# Amplifier_1.net
KiCad netlist of a schematic drawn in Altium Designer
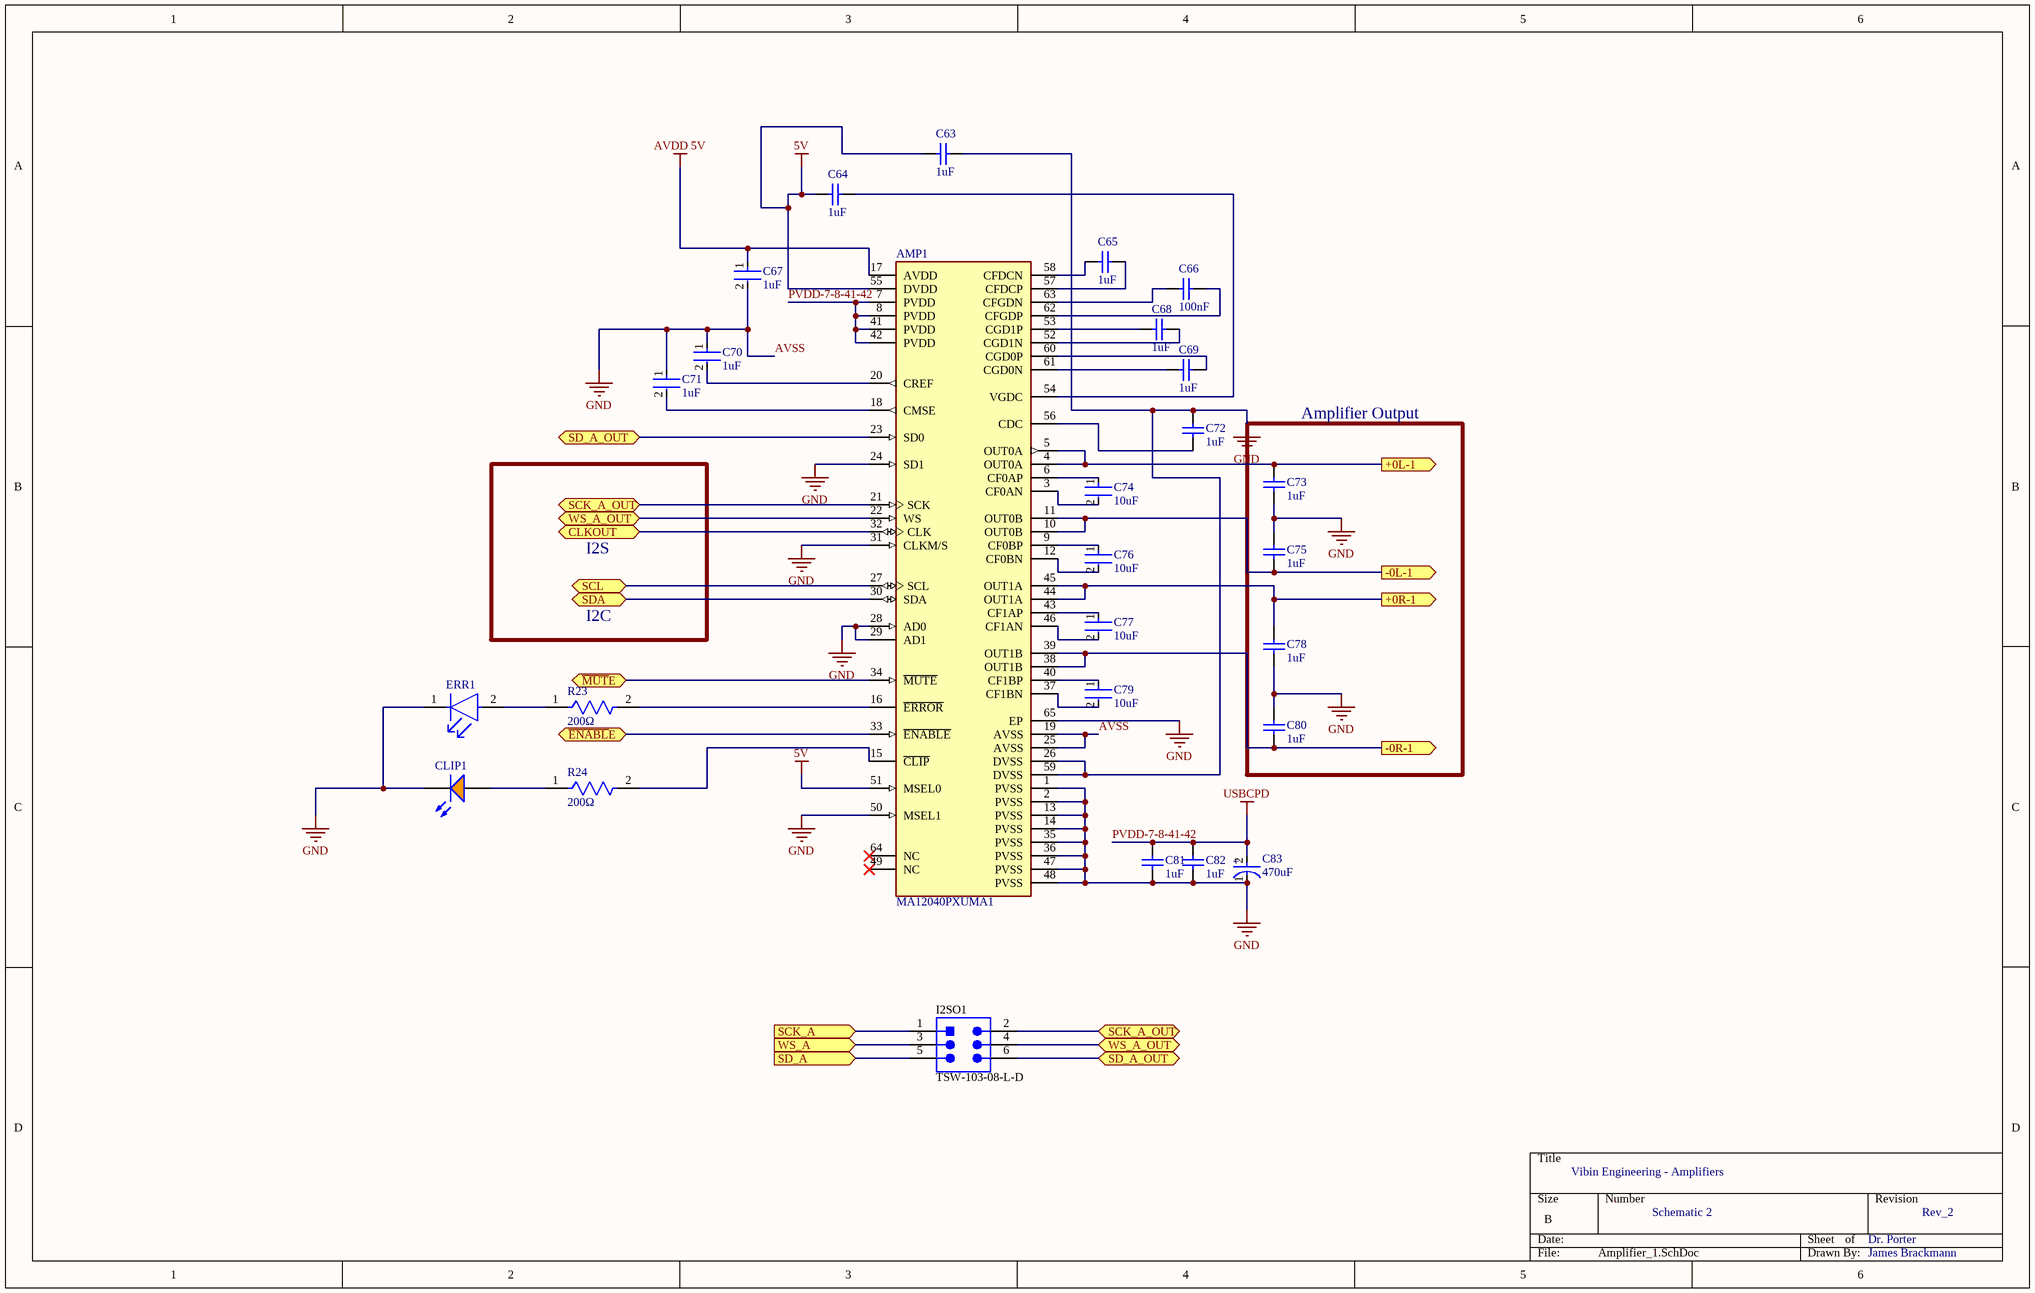
[diagram p0: Amplifier_1.SchDoc]

(export (version "E")
  (design (tool "Eeschema 10.0.6"))
  (components
    (comp (ref "AMP1")
      (value "MA12040PXUMA1")
      (footprint "FP-PG-VQFN-64-IPC_B")
      (description "IC AMP CLASS D STEREO 40W 64QFN")
      (fields
        (field (name "MANUFACTURER") "Infineon")
        (field (name "OCTOPART") "https://octopart.com/ma12040pxuma1-infineon-95984592")
      )
      (libsource (lib "Altium Content Vault") (part "7beef1d240aa861170d3bde7275adf3"))
    )
    (comp (ref "C63")
      (value "1uF")
      (footprint "CAPC1608X90X35LL15T15")
      (description "C0603C105K4RACTU")
      (fields (field (name "MANUFACTURER") "Kemet"))
      (libsource (lib "Altium Content Vault") (part "CAP"))
    )
    (comp (ref "C64")
      (value "1uF")
      (footprint "CAPC1608X90X35LL15T15")
      (description "C0603C105K4RACTU")
      (fields (field (name "MANUFACTURER") "Kemet"))
      (libsource (lib "Altium Content Vault") (part "CAP"))
    )
    (comp (ref "C65")
      (value "1uF")
      (footprint "CAPC1608X90X35LL15T15")
      (description "C0603C105K4RACTU")
      (fields (field (name "MANUFACTURER") "Kemet"))
      (libsource (lib "Altium Content Vault") (part "CAP"))
    )
    (comp (ref "C66")
      (value "100nF")
      (footprint "CAPC1608X90X35ML10T15")
      (fields
        (field (name "TOLERANCE") "10%")
        (field (name "VOLTAGE") "50V")
        (field (name "MANUFACTURER") "Murata")
      )
      (libsource (lib "Altium Content Vault") (part "CAP-NP-2"))
    )
    (comp (ref "C67")
      (value "1uF")
      (footprint "FP-GRM15-0_1-MFG")
      (description "CAP CER 1UF 10V X5R 0402         GRM155R61A105KE15D")
      (fields
        (field (name "OCTOPART") "https://octopart.com/grm155r61a105ke15d-murata-197442")
        (field (name "MANUFACTURER PART NUMBER") "GRM155R61A105KE15D")
      )
      (libsource (lib "Altium Content Vault") (part "02cd4be3c70576c341d710602a673aa"))
    )
    (comp (ref "C68")
      (value "1uF")
      (footprint "CAPC1608X90X35LL15T15")
      (description "C0603C105K4RACTU")
      (fields (field (name "MANUFACTURER") "Kemet"))
      (libsource (lib "Altium Content Vault") (part "CAP"))
    )
    (comp (ref "C69")
      (value "1uF")
      (footprint "CAPC1608X90X35LL15T15")
      (description "C0603C105K4RACTU")
      (fields (field (name "MANUFACTURER") "Kemet"))
      (libsource (lib "Altium Content Vault") (part "CAP"))
    )
    (comp (ref "C70")
      (value "1uF")
      (footprint "FP-GRM15-0_1-MFG")
      (description "CAP CER 1UF 10V X5R 0402         GRM155R61A105KE15D")
      (fields
        (field (name "OCTOPART") "https://octopart.com/grm155r61a105ke15d-murata-197442")
        (field (name "MANUFACTURER PART NUMBER") "GRM155R61A105KE15D")
      )
      (libsource (lib "Altium Content Vault") (part "02cd4be3c70576c341d710602a673aa"))
    )
    (comp (ref "C71")
      (value "1uF")
      (footprint "FP-GRM15-0_1-MFG")
      (description "CAP CER 1UF 10V X5R 0402         GRM155R61A105KE15D")
      (fields
        (field (name "OCTOPART") "https://octopart.com/grm155r61a105ke15d-murata-197442")
        (field (name "MANUFACTURER PART NUMBER") "GRM155R61A105KE15D")
      )
      (libsource (lib "Altium Content Vault") (part "02cd4be3c70576c341d710602a673aa"))
    )
    (comp (ref "C72")
      (value "1uF")
      (footprint "CAPC1608X90X35LL15T15")
      (description "C0603C105K4RACTU")
      (fields (field (name "MANUFACTURER") "Kemet"))
      (libsource (lib "Altium Content Vault") (part "CAP"))
    )
    (comp (ref "C73")
      (value "1uF")
      (footprint "CAPC1608X90X35LL15T15")
      (description "C0603C105K4RACTU")
      (fields (field (name "MANUFACTURER") "Kemet"))
      (libsource (lib "Altium Content Vault") (part "CAP"))
    )
    (comp (ref "C74")
      (value "10uF")
      (footprint "FP-1210-L_3_3_0_4-W_2_5_0-MFG")
      (description "General Purpose Ceramic Capacitor, 1210, 10uF, 10%, X5R, 15%, 25V        12103D106KAT2A")
      (fields (field (name "VOLTAGE") "25V") (field (name "TOLERANCE") "10%"))
      (libsource (lib "Altium Content Vault") (part "b4654b650e69147ec39a6b967a45e02"))
    )
    (comp (ref "C75")
      (value "1uF")
      (footprint "CAPC1608X90X35LL15T15")
      (description "C0603C105K4RACTU")
      (fields (field (name "MANUFACTURER") "Kemet"))
      (libsource (lib "Altium Content Vault") (part "CAP"))
    )
    (comp (ref "C76")
      (value "10uF")
      (footprint "FP-1210-L_3_3_0_4-W_2_5_0-MFG")
      (description "General Purpose Ceramic Capacitor, 1210, 10uF, 10%, X5R, 15%, 25V        12103D106KAT2A")
      (fields (field (name "VOLTAGE") "25V") (field (name "TOLERANCE") "10%"))
      (libsource (lib "Altium Content Vault") (part "b4654b650e69147ec39a6b967a45e02"))
    )
    (comp (ref "C77")
      (value "10uF")
      (footprint "FP-1210-L_3_3_0_4-W_2_5_0-MFG")
      (description "General Purpose Ceramic Capacitor, 1210, 10uF, 10%, X5R, 15%, 25V        12103D106KAT2A")
      (fields (field (name "VOLTAGE") "25V") (field (name "TOLERANCE") "10%"))
      (libsource (lib "Altium Content Vault") (part "b4654b650e69147ec39a6b967a45e02"))
    )
    (comp (ref "C78")
      (value "1uF")
      (footprint "CAPC1608X90X35LL15T15")
      (description "C0603C105K4RACTU")
      (fields (field (name "MANUFACTURER") "Kemet"))
      (libsource (lib "Altium Content Vault") (part "CAP"))
    )
    (comp (ref "C79")
      (value "10uF")
      (footprint "FP-1210-L_3_3_0_4-W_2_5_0-MFG")
      (description "General Purpose Ceramic Capacitor, 1210, 10uF, 10%, X5R, 15%, 25V        12103D106KAT2A")
      (fields (field (name "VOLTAGE") "25V") (field (name "TOLERANCE") "10%"))
      (libsource (lib "Altium Content Vault") (part "b4654b650e69147ec39a6b967a45e02"))
    )
    (comp (ref "C80")
      (value "1uF")
      (footprint "CAPC1608X90X35LL15T15")
      (description "C0603C105K4RACTU")
      (fields (field (name "MANUFACTURER") "Kemet"))
      (libsource (lib "Altium Content Vault") (part "CAP"))
    )
    (comp (ref "C81")
      (value "1uF")
      (footprint "CAPC1608X90X35LL15T15")
      (description "C0603C105K4RACTU")
      (fields (field (name "MANUFACTURER") "Kemet"))
      (libsource (lib "Altium Content Vault") (part "CAP"))
    )
    (comp (ref "C82")
      (value "1uF")
      (footprint "CAPC1608X90X35LL15T15")
      (description "C0603C105K4RACTU")
      (fields (field (name "MANUFACTURER") "Kemet"))
      (libsource (lib "Altium Content Vault") (part "CAP"))
    )
    (comp (ref "C83")
      (value "470uF")
      (footprint "FP-OS-CON-SMT-E12-MFG")
      (description "Conductive Polymer Aluminum Solid Capacitors (OS-CON) 470uF ±20% 20V      20SVPK470M")
      (fields (field (name "TOLERANCE") "20%"))
      (libsource (lib "Altium Content Vault") (part "a00bbbee19879c290e62620ae7e47b1"))
    )
    (comp (ref "CLIP1")
      (value "TLMO1100-GS08")
      (footprint "VISH-TLMX1100-2_V")
      (libsource (lib "Altium Content Vault") (part "LED-ORANGE-AK-2"))
    )
    (comp (ref "ERR1")
      (value "LTST-C190GKT")
      (footprint "FP-LTST-C190GKT-MFG")
      (description "LED GREEN CLEAR CHIP SMD       LTST-C190GKT")
      (fields (field (name "VOLTAGE") "2V"))
      (libsource (lib "Altium Content Vault") (part "8706943c75ba83719d021d2fdc84c58"))
    )
    (comp (ref "I2SO1")
      (value "TSW-103-08-L-D")
      (footprint "SMTC-TSW-103-08-L-D_V")
      (fields (field (name "MANUFACTURER") "Samtec"))
      (libsource (lib "Altium Content Vault") (part "CN-2P-M-R6"))
    )
    (comp (ref "R23")
      (value "200Ω")
      (footprint "FP-ERJ2RK-IPC_A")
      (description "RES SMD 200 OHM 1% 1/10W 0402      ERJ-2RKF2000X")
      (fields (field (name "TOLERANCE") "1%"))
      (libsource (lib "Altium Content Vault") (part "1029c3af85768c4190bb7ad29bc67b5"))
    )
    (comp (ref "R24")
      (value "200Ω")
      (footprint "FP-ERJ2RK-IPC_A")
      (description "RES SMD 200 OHM 1% 1/10W 0402    ERJ-2RKF2000X")
      (fields (field (name "TOLERANCE") "1%"))
      (libsource (lib "Altium Content Vault") (part "1029c3af85768c4190bb7ad29bc67b5"))
    )
  )
  (nets
    (net (code "1") (name "/+0L-1") (class "Default")
      (node (ref "AMP1") (pin "4") (pinfunction "OUT0A_4") (pintype "passive"))
      (node (ref "AMP1") (pin "5") (pinfunction "OUT0A_5") (pintype "output"))
      (node (ref "C73") (pin "1") (pinfunction "1_1") (pintype "passive"))
    )
    (net (code "2") (name "/+0R-1") (class "Default")
      (node (ref "AMP1") (pin "44") (pinfunction "OUT1A_44") (pintype "passive"))
      (node (ref "AMP1") (pin "45") (pinfunction "OUT1A_45") (pintype "passive"))
      (node (ref "C78") (pin "1") (pinfunction "1_1") (pintype "passive"))
    )
    (net (code "3") (name "/-0L-1") (class "Default")
      (node (ref "AMP1") (pin "10") (pinfunction "OUT0B_10") (pintype "passive"))
      (node (ref "AMP1") (pin "11") (pinfunction "OUT0B_11") (pintype "passive"))
      (node (ref "C75") (pin "2") (pinfunction "2_2") (pintype "passive"))
    )
    (net (code "4") (name "/-0R-1") (class "Default")
      (node (ref "AMP1") (pin "38") (pinfunction "OUT1B_38") (pintype "passive"))
      (node (ref "AMP1") (pin "39") (pinfunction "OUT1B_39") (pintype "passive"))
      (node (ref "C80") (pin "2") (pinfunction "2_2") (pintype "passive"))
    )
    (net (code "5") (name "/CLKOUT") (class "Default")
      (node (ref "AMP1") (pin "32") (pinfunction "CLK_32") (pintype "bidirectional"))
    )
    (net (code "6") (name "/SCK_A") (class "Default")
      (node (ref "I2SO1") (pin "1") (pinfunction "1_1") (pintype "passive"))
    )
    (net (code "7") (name "/SCK_A_OUT") (class "Default")
      (node (ref "AMP1") (pin "21") (pinfunction "SCK_21") (pintype "input"))
      (node (ref "I2SO1") (pin "2") (pinfunction "2_2") (pintype "passive"))
    )
    (net (code "8") (name "/SCL") (class "Default")
      (node (ref "AMP1") (pin "27") (pinfunction "SCL_27") (pintype "bidirectional"))
    )
    (net (code "9") (name "/SDA") (class "Default")
      (node (ref "AMP1") (pin "30") (pinfunction "SDA_30") (pintype "bidirectional"))
    )
    (net (code "10") (name "/SD_A") (class "Default")
      (node (ref "I2SO1") (pin "5") (pinfunction "5_5") (pintype "passive"))
    )
    (net (code "11") (name "/SD_A_OUT") (class "Default")
      (node (ref "AMP1") (pin "23") (pinfunction "SD0_23") (pintype "input"))
      (node (ref "I2SO1") (pin "6") (pinfunction "6_6") (pintype "passive"))
    )
    (net (code "12") (name "/WS_A") (class "Default")
      (node (ref "I2SO1") (pin "3") (pinfunction "3_3") (pintype "passive"))
    )
    (net (code "13") (name "/WS_A_OUT") (class "Default")
      (node (ref "AMP1") (pin "22") (pinfunction "WS_22") (pintype "input"))
      (node (ref "I2SO1") (pin "4") (pinfunction "4_4") (pintype "passive"))
    )
    (net (code "14") (name "/~{ENABL}E") (class "Default")
      (node (ref "AMP1") (pin "33") (pinfunction "~{ENABLE}_33") (pintype "input"))
    )
    (net (code "15") (name "/~{MUT}E") (class "Default")
      (node (ref "AMP1") (pin "34") (pinfunction "~{MUTE}_34") (pintype "input"))
    )
    (net (code "16") (name "5V") (class "Default")
      (node (ref "AMP1") (pin "51") (pinfunction "MSEL0_51") (pintype "input"))
      (node (ref "AMP1") (pin "55") (pinfunction "DVDD_55") (pintype "power_in"))
      (node (ref "C63") (pin "2") (pinfunction "2_2") (pintype "passive"))
      (node (ref "C64") (pin "1") (pinfunction "1_1") (pintype "passive"))
    )
    (net (code "17") (name "AVDD 5V") (class "Default")
      (node (ref "AMP1") (pin "17") (pinfunction "AVDD_17") (pintype "power_in"))
      (node (ref "C67") (pin "1") (pinfunction "1_1") (pintype "passive"))
    )
    (net (code "18") (name "GND") (class "Default")
      (node (ref "AMP1") (pin "1") (pinfunction "PVSS_1") (pintype "power_in"))
      (node (ref "AMP1") (pin "13") (pinfunction "PVSS_13") (pintype "power_in"))
      (node (ref "AMP1") (pin "14") (pinfunction "PVSS_14") (pintype "power_in"))
      (node (ref "AMP1") (pin "19") (pinfunction "AVSS_19") (pintype "power_in"))
      (node (ref "AMP1") (pin "2") (pinfunction "PVSS_2") (pintype "power_in"))
      (node (ref "AMP1") (pin "24") (pinfunction "SD1_24") (pintype "input"))
      (node (ref "AMP1") (pin "25") (pinfunction "AVSS_25") (pintype "power_in"))
      (node (ref "AMP1") (pin "26") (pinfunction "DVSS_26") (pintype "power_in"))
      (node (ref "AMP1") (pin "28") (pinfunction "AD0_28") (pintype "input"))
      (node (ref "AMP1") (pin "29") (pinfunction "AD1_29") (pintype "passive"))
      (node (ref "AMP1") (pin "31") (pinfunction "CLKM/S_31") (pintype "input"))
      (node (ref "AMP1") (pin "35") (pinfunction "PVSS_35") (pintype "power_in"))
      (node (ref "AMP1") (pin "36") (pinfunction "PVSS_36") (pintype "power_in"))
      (node (ref "AMP1") (pin "47") (pinfunction "PVSS_47") (pintype "power_in"))
      (node (ref "AMP1") (pin "48") (pinfunction "PVSS_48") (pintype "power_in"))
      (node (ref "AMP1") (pin "50") (pinfunction "MSEL1_50") (pintype "input"))
      (node (ref "AMP1") (pin "59") (pinfunction "DVSS_59") (pintype "power_in"))
      (node (ref "AMP1") (pin "65") (pinfunction "EP_65") (pintype "power_in"))
      (node (ref "C63") (pin "1") (pinfunction "1_1") (pintype "passive"))
      (node (ref "C67") (pin "2") (pinfunction "2_2") (pintype "passive"))
      (node (ref "C70") (pin "1") (pinfunction "1_1") (pintype "passive"))
      (node (ref "C71") (pin "1") (pinfunction "1_1") (pintype "passive"))
      (node (ref "C72") (pin "1") (pinfunction "1_1") (pintype "passive"))
      (node (ref "C73") (pin "2") (pinfunction "2_2") (pintype "passive"))
      (node (ref "C75") (pin "1") (pinfunction "1_1") (pintype "passive"))
      (node (ref "C78") (pin "2") (pinfunction "2_2") (pintype "passive"))
      (node (ref "C80") (pin "1") (pinfunction "1_1") (pintype "passive"))
      (node (ref "C81") (pin "2") (pinfunction "2_2") (pintype "passive"))
      (node (ref "C82") (pin "2") (pinfunction "2_2") (pintype "passive"))
      (node (ref "C83") (pin "1") (pinfunction "C_1") (pintype "passive"))
      (node (ref "CLIP1") (pin "2") (pinfunction "K_2") (pintype "passive"))
      (node (ref "ERR1") (pin "1") (pinfunction "C_1") (pintype "passive"))
    )
    (net (code "19") (name "Net-(AMP1-CDC)") (class "Default")
      (node (ref "AMP1") (pin "56") (pinfunction "CDC_56") (pintype "passive"))
      (node (ref "C72") (pin "2") (pinfunction "2_2") (pintype "passive"))
    )
    (net (code "20") (name "Net-(AMP1-CF0AN)") (class "Default")
      (node (ref "AMP1") (pin "3") (pinfunction "CF0AN_3") (pintype "passive"))
      (node (ref "C74") (pin "2") (pinfunction "2_2") (pintype "passive"))
    )
    (net (code "21") (name "Net-(AMP1-CF0AP)") (class "Default")
      (node (ref "AMP1") (pin "6") (pinfunction "CF0AP_6") (pintype "passive"))
      (node (ref "C74") (pin "1") (pinfunction "1_1") (pintype "passive"))
    )
    (net (code "22") (name "Net-(AMP1-CF0BN)") (class "Default")
      (node (ref "AMP1") (pin "12") (pinfunction "CF0BN_12") (pintype "passive"))
      (node (ref "C76") (pin "2") (pinfunction "2_2") (pintype "passive"))
    )
    (net (code "23") (name "Net-(AMP1-CF0BP)") (class "Default")
      (node (ref "AMP1") (pin "9") (pinfunction "CF0BP_9") (pintype "passive"))
      (node (ref "C76") (pin "1") (pinfunction "1_1") (pintype "passive"))
    )
    (net (code "24") (name "Net-(AMP1-CF1AN)") (class "Default")
      (node (ref "AMP1") (pin "46") (pinfunction "CF1AN_46") (pintype "passive"))
      (node (ref "C77") (pin "2") (pinfunction "2_2") (pintype "passive"))
    )
    (net (code "25") (name "Net-(AMP1-CF1AP)") (class "Default")
      (node (ref "AMP1") (pin "43") (pinfunction "CF1AP_43") (pintype "passive"))
      (node (ref "C77") (pin "1") (pinfunction "1_1") (pintype "passive"))
    )
    (net (code "26") (name "Net-(AMP1-CF1BN)") (class "Default")
      (node (ref "AMP1") (pin "37") (pinfunction "CF1BN_37") (pintype "passive"))
      (node (ref "C79") (pin "2") (pinfunction "2_2") (pintype "passive"))
    )
    (net (code "27") (name "Net-(AMP1-CF1BP)") (class "Default")
      (node (ref "AMP1") (pin "40") (pinfunction "CF1BP_40") (pintype "passive"))
      (node (ref "C79") (pin "1") (pinfunction "1_1") (pintype "passive"))
    )
    (net (code "28") (name "Net-(AMP1-CFDCN)") (class "Default")
      (node (ref "AMP1") (pin "58") (pinfunction "CFDCN_58") (pintype "passive"))
      (node (ref "C65") (pin "2") (pinfunction "2_2") (pintype "passive"))
    )
    (net (code "29") (name "Net-(AMP1-CFDCP)") (class "Default")
      (node (ref "AMP1") (pin "57") (pinfunction "CFDCP_57") (pintype "passive"))
      (node (ref "C65") (pin "1") (pinfunction "1_1") (pintype "passive"))
    )
    (net (code "30") (name "Net-(AMP1-CFGDN)") (class "Default")
      (node (ref "AMP1") (pin "63") (pinfunction "CFGDN_63") (pintype "passive"))
      (node (ref "C66") (pin "2") (pinfunction "2_2") (pintype "passive"))
    )
    (net (code "31") (name "Net-(AMP1-CFGDP)") (class "Default")
      (node (ref "AMP1") (pin "62") (pinfunction "CFGDP_62") (pintype "passive"))
      (node (ref "C66") (pin "1") (pinfunction "1_1") (pintype "passive"))
    )
    (net (code "32") (name "Net-(AMP1-CGD0N)") (class "Default")
      (node (ref "AMP1") (pin "61") (pinfunction "CGD0N_61") (pintype "passive"))
      (node (ref "C69") (pin "2") (pinfunction "2_2") (pintype "passive"))
    )
    (net (code "33") (name "Net-(AMP1-CGD0P)") (class "Default")
      (node (ref "AMP1") (pin "60") (pinfunction "CGD0P_60") (pintype "passive"))
      (node (ref "C69") (pin "1") (pinfunction "1_1") (pintype "passive"))
    )
    (net (code "34") (name "Net-(AMP1-CGD1N)") (class "Default")
      (node (ref "AMP1") (pin "52") (pinfunction "CGD1N_52") (pintype "passive"))
      (node (ref "C68") (pin "1") (pinfunction "1_1") (pintype "passive"))
    )
    (net (code "35") (name "Net-(AMP1-CGD1P)") (class "Default")
      (node (ref "AMP1") (pin "53") (pinfunction "CGD1P_53") (pintype "passive"))
      (node (ref "C68") (pin "2") (pinfunction "2_2") (pintype "passive"))
    )
    (net (code "36") (name "Net-(AMP1-CMSE)") (class "Default")
      (node (ref "AMP1") (pin "18") (pinfunction "CMSE_18") (pintype "output"))
      (node (ref "C71") (pin "2") (pinfunction "2_2") (pintype "passive"))
    )
    (net (code "37") (name "Net-(AMP1-CREF)") (class "Default")
      (node (ref "AMP1") (pin "20") (pinfunction "CREF_20") (pintype "output"))
      (node (ref "C70") (pin "2") (pinfunction "2_2") (pintype "passive"))
    )
    (net (code "38") (name "Net-(AMP1-VGDC)") (class "Default")
      (node (ref "AMP1") (pin "54") (pinfunction "VGDC_54") (pintype "power_in"))
      (node (ref "C64") (pin "2") (pinfunction "2_2") (pintype "passive"))
    )
    (net (code "39") (name "Net-(AMP1-~{CLIP})") (class "Default")
      (node (ref "AMP1") (pin "15") (pinfunction "~{CLIP}_15") (pintype "open_collector"))
      (node (ref "R24") (pin "2") (pinfunction "2_2") (pintype "passive"))
    )
    (net (code "40") (name "Net-(AMP1-~{ERROR})") (class "Default")
      (node (ref "AMP1") (pin "16") (pinfunction "~{ERROR}_16") (pintype "open_collector"))
      (node (ref "R23") (pin "2") (pinfunction "2_2") (pintype "passive"))
    )
    (net (code "41") (name "Net-(CLIP1-A)") (class "Default")
      (node (ref "CLIP1") (pin "1") (pinfunction "A_1") (pintype "passive"))
      (node (ref "R24") (pin "1") (pinfunction "1_1") (pintype "passive"))
    )
    (net (code "42") (name "Net-(ERR1-A)") (class "Default")
      (node (ref "ERR1") (pin "2") (pinfunction "A_2") (pintype "passive"))
      (node (ref "R23") (pin "1") (pinfunction "1_1") (pintype "passive"))
    )
    (net (code "43") (name "USBCPD") (class "Default")
      (node (ref "AMP1") (pin "41") (pinfunction "PVDD_41") (pintype "power_in"))
      (node (ref "AMP1") (pin "42") (pinfunction "PVDD_42") (pintype "power_in"))
      (node (ref "AMP1") (pin "7") (pinfunction "PVDD_7") (pintype "power_in"))
      (node (ref "AMP1") (pin "8") (pinfunction "PVDD_8") (pintype "power_in"))
      (node (ref "C81") (pin "1") (pinfunction "1_1") (pintype "passive"))
      (node (ref "C82") (pin "1") (pinfunction "1_1") (pintype "passive"))
      (node (ref "C83") (pin "2") (pinfunction "A_2") (pintype "passive"))
    )
    (net (code "44") (name "unconnected-(AMP1-NC-Pad49)") (class "Default")
      (node (ref "AMP1") (pin "49") (pinfunction "NC_49") (pintype "passive+no_connect"))
    )
    (net (code "45") (name "unconnected-(AMP1-NC-Pad64)") (class "Default")
      (node (ref "AMP1") (pin "64") (pinfunction "NC_64") (pintype "passive+no_connect"))
    )
  )
)
